# PWR_CORE.net
KiCad netlist of a schematic drawn in Altium Designer
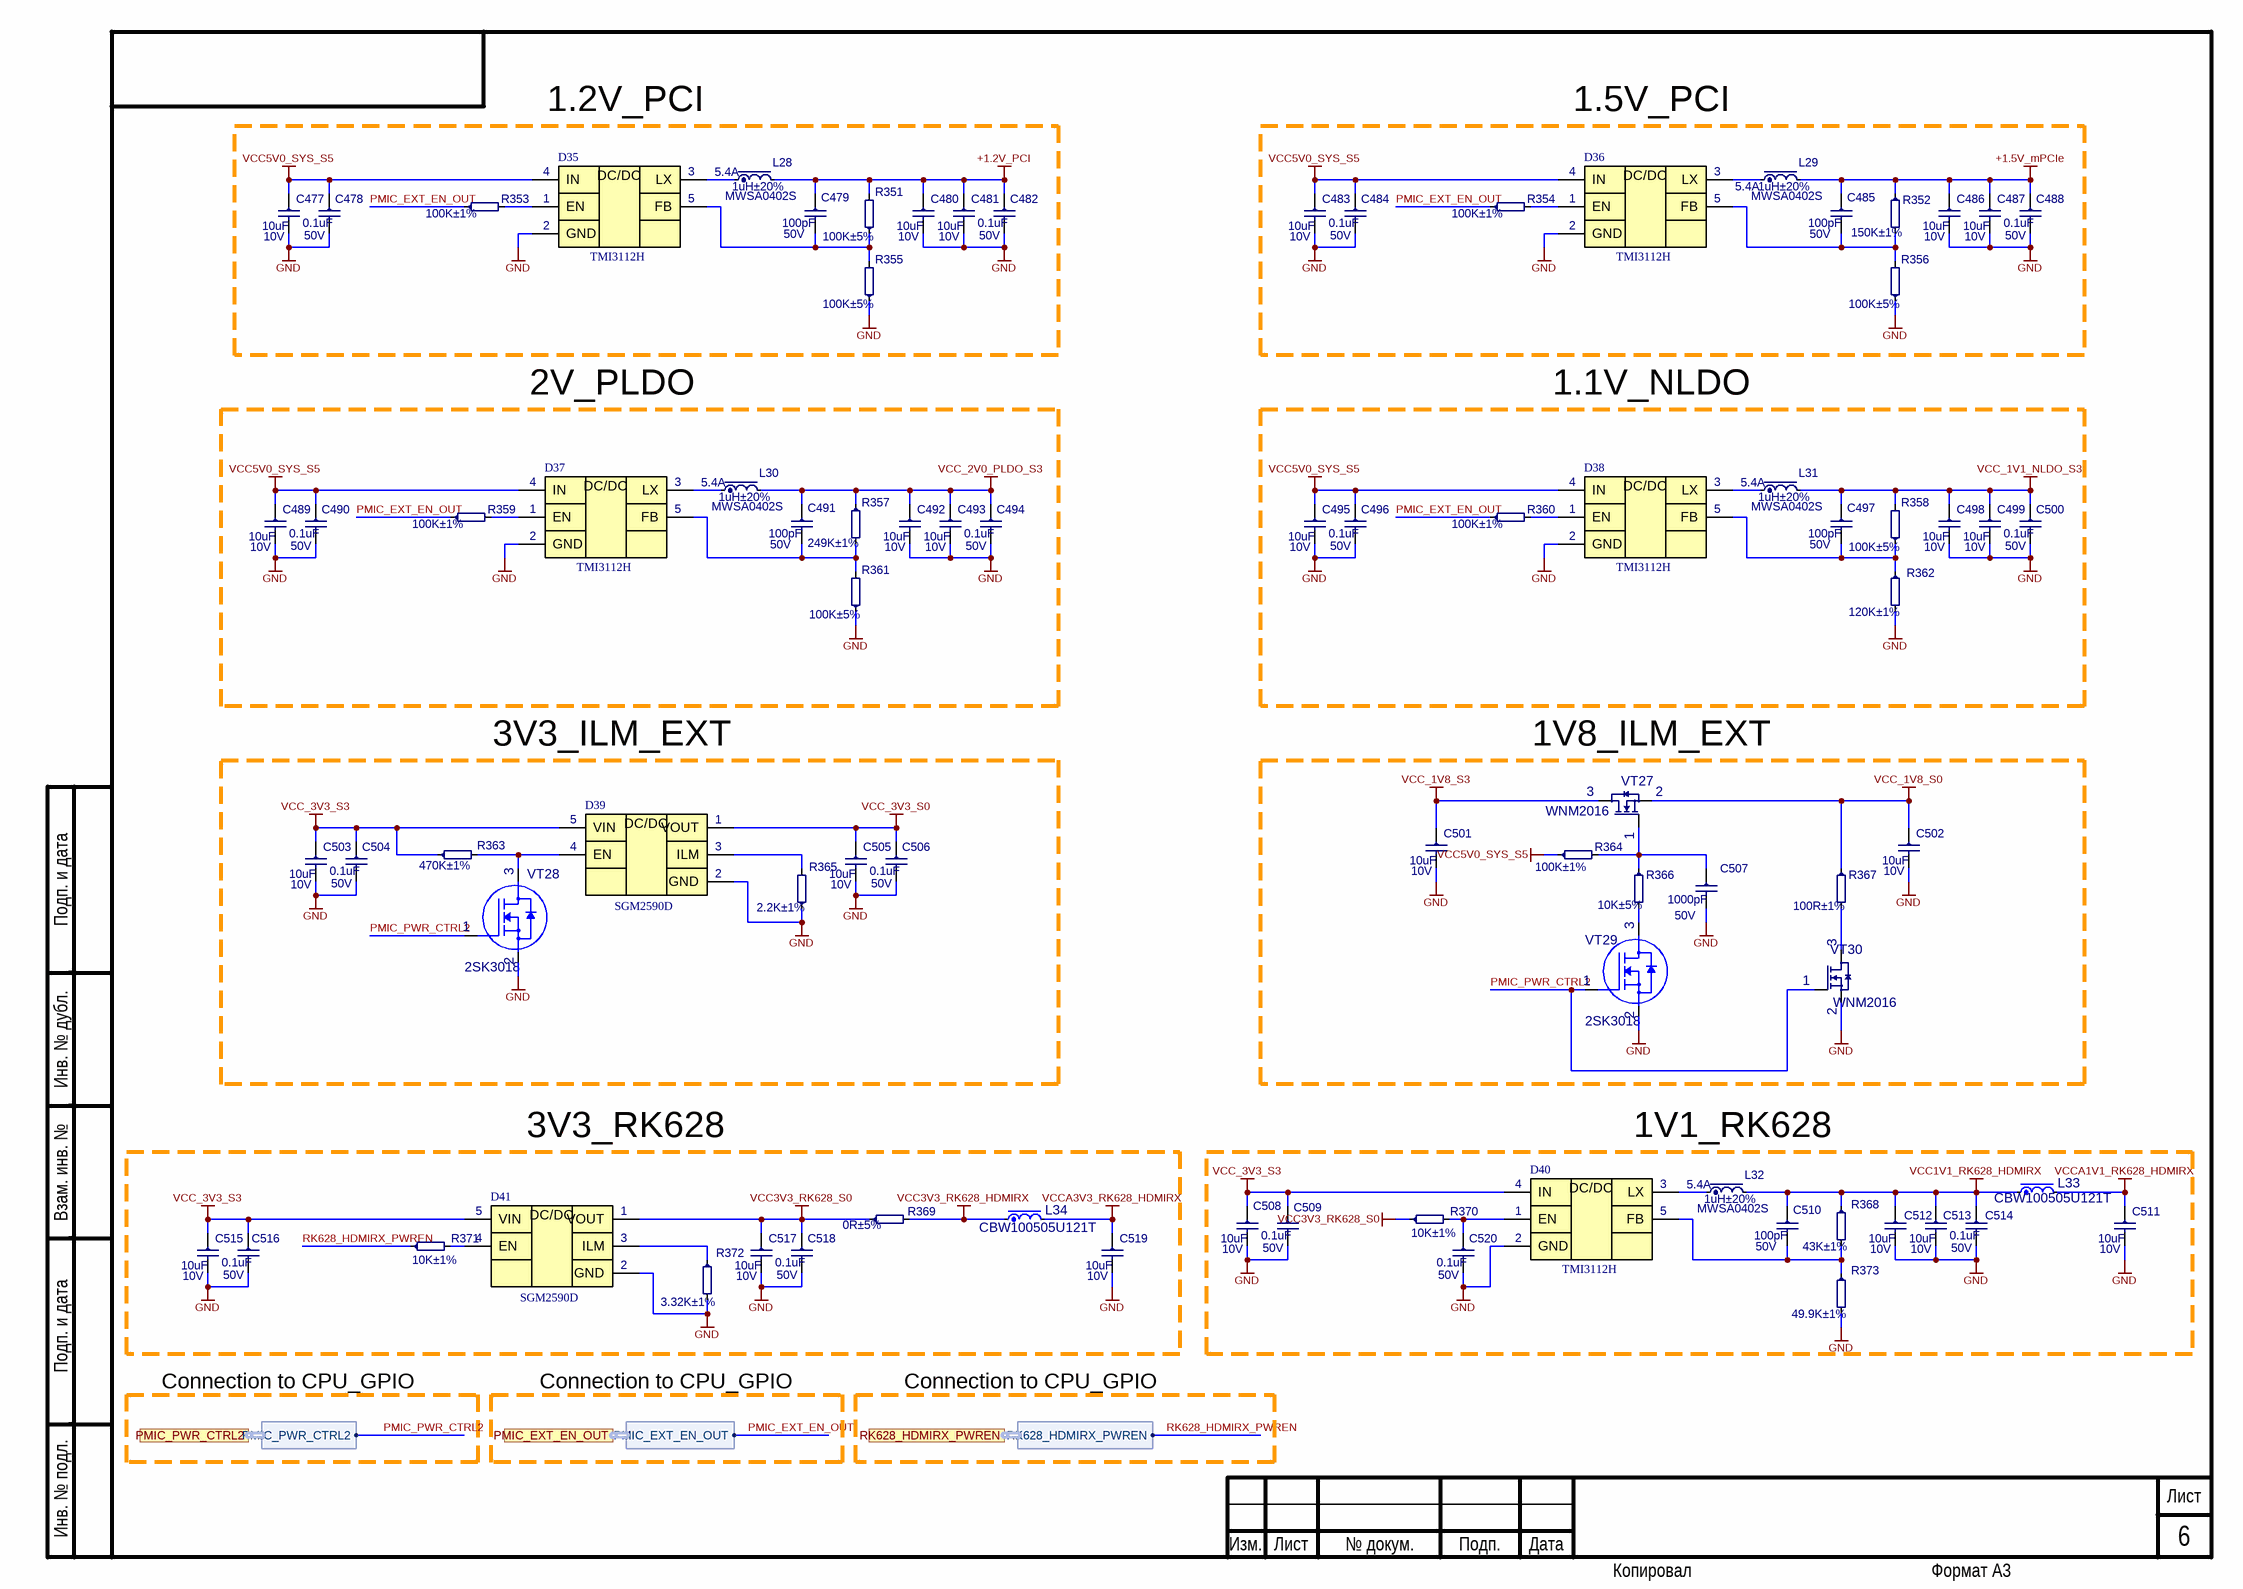
[diagram p0: PWR_CORE.SchDoc]

(export (version "E")
  (design (tool "Eeschema 10.0.6"))
  (components
    (comp (ref "C477")
      (value "10uF")
      (footprint "C0603")
      (fields
        (field (name "VOLTAGE") "10V")
        (field (name "PART NUMBER") "0603-X5R-10V-10uF±10%")
        (field (name "TOLERANCE") "10%")
        (field (name "MANUFACTURER") "Yageo")
      )
      (libsource (lib "ATB") (part "C"))
    )
    (comp (ref "C478")
      (value "0.1uF")
      (footprint "C0402")
      (fields
        (field (name "VOLTAGE") "50V")
        (field (name "PART NUMBER") "0402-X5R-50V-0.1uF±10%")
        (field (name "TOLERANCE") "10%")
        (field (name "MANUFACTURER") "Yageo")
      )
      (libsource (lib "ATB") (part "C"))
    )
    (comp (ref "C479")
      (value "100pF")
      (footprint "C0402")
      (fields
        (field (name "VOLTAGE") "50V")
        (field (name "PART NUMBER") "0402-NP0-50V-100pF±5%")
        (field (name "TOLERANCE") "5%")
        (field (name "MANUFACTURER") "Yageo")
      )
      (libsource (lib "ATB") (part "C"))
    )
    (comp (ref "C480")
      (value "10uF")
      (footprint "C0603")
      (fields
        (field (name "VOLTAGE") "10V")
        (field (name "PART NUMBER") "0603-X5R-10V-10uF±10%")
        (field (name "TOLERANCE") "10%")
        (field (name "MANUFACTURER") "Yageo")
      )
      (libsource (lib "ATB") (part "C"))
    )
    (comp (ref "C481")
      (value "10uF")
      (footprint "C0603")
      (fields
        (field (name "VOLTAGE") "10V")
        (field (name "PART NUMBER") "0603-X5R-10V-10uF±10%")
        (field (name "TOLERANCE") "10%")
        (field (name "MANUFACTURER") "Yageo")
      )
      (libsource (lib "ATB") (part "C"))
    )
    (comp (ref "C482")
      (value "0.1uF")
      (footprint "C0402")
      (fields
        (field (name "VOLTAGE") "50V")
        (field (name "PART NUMBER") "0402-X5R-50V-0.1uF±10%")
        (field (name "TOLERANCE") "10%")
        (field (name "MANUFACTURER") "Yageo")
      )
      (libsource (lib "ATB") (part "C"))
    )
    (comp (ref "C483")
      (value "10uF")
      (footprint "C0603")
      (fields
        (field (name "VOLTAGE") "10V")
        (field (name "PART NUMBER") "0603-X5R-10V-10uF±10%")
        (field (name "TOLERANCE") "10%")
        (field (name "MANUFACTURER") "Yageo")
      )
      (libsource (lib "ATB") (part "C"))
    )
    (comp (ref "C484")
      (value "0.1uF")
      (footprint "C0402")
      (fields
        (field (name "VOLTAGE") "50V")
        (field (name "PART NUMBER") "0402-X5R-50V-0.1uF±10%")
        (field (name "TOLERANCE") "10%")
        (field (name "MANUFACTURER") "Yageo")
      )
      (libsource (lib "ATB") (part "C"))
    )
    (comp (ref "C485")
      (value "100pF")
      (footprint "C0402")
      (fields
        (field (name "VOLTAGE") "50V")
        (field (name "PART NUMBER") "0402-NP0-50V-100pF±5%")
        (field (name "TOLERANCE") "5%")
        (field (name "MANUFACTURER") "Yageo")
      )
      (libsource (lib "ATB") (part "C"))
    )
    (comp (ref "C486")
      (value "10uF")
      (footprint "C0603")
      (fields
        (field (name "VOLTAGE") "10V")
        (field (name "PART NUMBER") "0603-X5R-10V-10uF±10%")
        (field (name "TOLERANCE") "10%")
        (field (name "MANUFACTURER") "Yageo")
      )
      (libsource (lib "ATB") (part "C"))
    )
    (comp (ref "C487")
      (value "10uF")
      (footprint "C0603")
      (fields
        (field (name "VOLTAGE") "10V")
        (field (name "PART NUMBER") "0603-X5R-10V-10uF±10%")
        (field (name "TOLERANCE") "10%")
        (field (name "MANUFACTURER") "Yageo")
      )
      (libsource (lib "ATB") (part "C"))
    )
    (comp (ref "C488")
      (value "0.1uF")
      (footprint "C0402")
      (fields
        (field (name "VOLTAGE") "50V")
        (field (name "PART NUMBER") "0402-X5R-50V-0.1uF±10%")
        (field (name "TOLERANCE") "10%")
        (field (name "MANUFACTURER") "Yageo")
      )
      (libsource (lib "ATB") (part "C"))
    )
    (comp (ref "C489")
      (value "10uF")
      (footprint "C0603")
      (fields
        (field (name "VOLTAGE") "10V")
        (field (name "PART NUMBER") "0603-X5R-10V-10uF±10%")
        (field (name "TOLERANCE") "10%")
        (field (name "MANUFACTURER") "Yageo")
      )
      (libsource (lib "ATB") (part "C"))
    )
    (comp (ref "C490")
      (value "0.1uF")
      (footprint "C0402")
      (fields
        (field (name "VOLTAGE") "50V")
        (field (name "PART NUMBER") "0402-X5R-50V-0.1uF±10%")
        (field (name "TOLERANCE") "10%")
        (field (name "MANUFACTURER") "Yageo")
      )
      (libsource (lib "ATB") (part "C"))
    )
    (comp (ref "C491")
      (value "100pF")
      (footprint "C0402")
      (fields
        (field (name "VOLTAGE") "50V")
        (field (name "PART NUMBER") "0402-NP0-50V-100pF±5%")
        (field (name "TOLERANCE") "5%")
        (field (name "MANUFACTURER") "Yageo")
      )
      (libsource (lib "ATB") (part "C"))
    )
    (comp (ref "C492")
      (value "10uF")
      (footprint "C0603")
      (fields
        (field (name "VOLTAGE") "10V")
        (field (name "PART NUMBER") "0603-X5R-10V-10uF±10%")
        (field (name "TOLERANCE") "10%")
        (field (name "MANUFACTURER") "Yageo")
      )
      (libsource (lib "ATB") (part "C"))
    )
    (comp (ref "C493")
      (value "10uF")
      (footprint "C0603")
      (fields
        (field (name "VOLTAGE") "10V")
        (field (name "PART NUMBER") "0603-X5R-10V-10uF±10%")
        (field (name "TOLERANCE") "10%")
        (field (name "MANUFACTURER") "Yageo")
      )
      (libsource (lib "ATB") (part "C"))
    )
    (comp (ref "C494")
      (value "0.1uF")
      (footprint "C0402")
      (fields
        (field (name "VOLTAGE") "50V")
        (field (name "PART NUMBER") "0402-X5R-50V-0.1uF±10%")
        (field (name "TOLERANCE") "10%")
        (field (name "MANUFACTURER") "Yageo")
      )
      (libsource (lib "ATB") (part "C"))
    )
    (comp (ref "C495")
      (value "10uF")
      (footprint "C0603")
      (fields
        (field (name "VOLTAGE") "10V")
        (field (name "PART NUMBER") "0603-X5R-10V-10uF±10%")
        (field (name "TOLERANCE") "10%")
        (field (name "MANUFACTURER") "Yageo")
      )
      (libsource (lib "ATB") (part "C"))
    )
    (comp (ref "C496")
      (value "0.1uF")
      (footprint "C0402")
      (fields
        (field (name "VOLTAGE") "50V")
        (field (name "PART NUMBER") "0402-X5R-50V-0.1uF±10%")
        (field (name "TOLERANCE") "10%")
        (field (name "MANUFACTURER") "Yageo")
      )
      (libsource (lib "ATB") (part "C"))
    )
    (comp (ref "C497")
      (value "100pF")
      (footprint "C0402")
      (fields
        (field (name "VOLTAGE") "50V")
        (field (name "PART NUMBER") "0402-NP0-50V-100pF±5%")
        (field (name "TOLERANCE") "5%")
        (field (name "MANUFACTURER") "Yageo")
      )
      (libsource (lib "ATB") (part "C"))
    )
    (comp (ref "C498")
      (value "10uF")
      (footprint "C0603")
      (fields
        (field (name "VOLTAGE") "10V")
        (field (name "PART NUMBER") "0603-X5R-10V-10uF±10%")
        (field (name "TOLERANCE") "10%")
        (field (name "MANUFACTURER") "Yageo")
      )
      (libsource (lib "ATB") (part "C"))
    )
    (comp (ref "C499")
      (value "10uF")
      (footprint "C0603")
      (fields
        (field (name "VOLTAGE") "10V")
        (field (name "PART NUMBER") "0603-X5R-10V-10uF±10%")
        (field (name "TOLERANCE") "10%")
        (field (name "MANUFACTURER") "Yageo")
      )
      (libsource (lib "ATB") (part "C"))
    )
    (comp (ref "C500")
      (value "0.1uF")
      (footprint "C0402")
      (fields
        (field (name "VOLTAGE") "50V")
        (field (name "PART NUMBER") "0402-X5R-50V-0.1uF±10%")
        (field (name "TOLERANCE") "10%")
        (field (name "MANUFACTURER") "Yageo")
      )
      (libsource (lib "ATB") (part "C"))
    )
    (comp (ref "C501")
      (value "10uF")
      (footprint "C0603")
      (fields
        (field (name "VOLTAGE") "10V")
        (field (name "PART NUMBER") "0603-X5R-10V-10uF±10%")
        (field (name "TOLERANCE") "10%")
        (field (name "MANUFACTURER") "Yageo")
      )
      (libsource (lib "ATB") (part "C"))
    )
    (comp (ref "C502")
      (value "10uF")
      (footprint "C0603")
      (fields
        (field (name "VOLTAGE") "10V")
        (field (name "PART NUMBER") "0603-X5R-10V-10uF±10%")
        (field (name "TOLERANCE") "10%")
        (field (name "MANUFACTURER") "Yageo")
      )
      (libsource (lib "ATB") (part "C"))
    )
    (comp (ref "C503")
      (value "10uF")
      (footprint "C0603")
      (fields
        (field (name "VOLTAGE") "10V")
        (field (name "PART NUMBER") "0603-X5R-10V-10uF±10%")
        (field (name "TOLERANCE") "10%")
        (field (name "MANUFACTURER") "Yageo")
      )
      (libsource (lib "ATB") (part "C"))
    )
    (comp (ref "C504")
      (value "0.1uF")
      (footprint "C0402")
      (fields
        (field (name "VOLTAGE") "50V")
        (field (name "PART NUMBER") "0402-X5R-50V-0.1uF±10%")
        (field (name "TOLERANCE") "10%")
        (field (name "MANUFACTURER") "Yageo")
      )
      (libsource (lib "ATB") (part "C"))
    )
    (comp (ref "C505")
      (value "10uF")
      (footprint "C0603")
      (fields
        (field (name "VOLTAGE") "10V")
        (field (name "PART NUMBER") "0603-X5R-10V-10uF±10%")
        (field (name "TOLERANCE") "10%")
        (field (name "MANUFACTURER") "Yageo")
      )
      (libsource (lib "ATB") (part "C"))
    )
    (comp (ref "C506")
      (value "0.1uF")
      (footprint "C0402")
      (fields
        (field (name "VOLTAGE") "50V")
        (field (name "PART NUMBER") "0402-X5R-50V-0.1uF±10%")
        (field (name "TOLERANCE") "10%")
        (field (name "MANUFACTURER") "Yageo")
      )
      (libsource (lib "ATB") (part "C"))
    )
    (comp (ref "C507")
      (value "1000pF")
      (footprint "C0402")
      (fields
        (field (name "VOLTAGE") "50V")
        (field (name "PART NUMBER") "0402-NP0-50V-1000pF±5%")
        (field (name "TOLERANCE") "5%")
        (field (name "MANUFACTURER") "Yageo")
      )
      (libsource (lib "ATB") (part "C"))
    )
    (comp (ref "C508")
      (value "10uF")
      (footprint "C0603")
      (fields
        (field (name "VOLTAGE") "10V")
        (field (name "PART NUMBER") "0603-X5R-10V-10uF±10%")
        (field (name "TOLERANCE") "10%")
        (field (name "MANUFACTURER") "Yageo")
      )
      (libsource (lib "ATB") (part "C"))
    )
    (comp (ref "C509")
      (value "0.1uF")
      (footprint "C0402")
      (fields
        (field (name "VOLTAGE") "50V")
        (field (name "PART NUMBER") "0402-X5R-50V-0.1uF±10%")
        (field (name "TOLERANCE") "10%")
        (field (name "MANUFACTURER") "Yageo")
      )
      (libsource (lib "ATB") (part "C"))
    )
    (comp (ref "C510")
      (value "100pF")
      (footprint "C0402")
      (fields
        (field (name "VOLTAGE") "50V")
        (field (name "PART NUMBER") "0402-NP0-50V-100pF±5%")
        (field (name "TOLERANCE") "5%")
        (field (name "MANUFACTURER") "Yageo")
      )
      (libsource (lib "ATB") (part "C"))
    )
    (comp (ref "C511")
      (value "10uF")
      (footprint "C0603")
      (fields
        (field (name "VOLTAGE") "10V")
        (field (name "PART NUMBER") "0603-X5R-10V-10uF±10%")
        (field (name "TOLERANCE") "10%")
        (field (name "MANUFACTURER") "Yageo")
      )
      (libsource (lib "ATB") (part "C"))
    )
    (comp (ref "C512")
      (value "10uF")
      (footprint "C0603")
      (fields
        (field (name "VOLTAGE") "10V")
        (field (name "PART NUMBER") "0603-X5R-10V-10uF±10%")
        (field (name "TOLERANCE") "10%")
        (field (name "MANUFACTURER") "Yageo")
      )
      (libsource (lib "ATB") (part "C"))
    )
    (comp (ref "C513")
      (value "10uF")
      (footprint "C0603")
      (fields
        (field (name "VOLTAGE") "10V")
        (field (name "PART NUMBER") "0603-X5R-10V-10uF±10%")
        (field (name "TOLERANCE") "10%")
        (field (name "MANUFACTURER") "Yageo")
      )
      (libsource (lib "ATB") (part "C"))
    )
    (comp (ref "C514")
      (value "0.1uF")
      (footprint "C0402")
      (fields
        (field (name "VOLTAGE") "50V")
        (field (name "PART NUMBER") "0402-X5R-50V-0.1uF±10%")
        (field (name "TOLERANCE") "10%")
        (field (name "MANUFACTURER") "Yageo")
      )
      (libsource (lib "ATB") (part "C"))
    )
    (comp (ref "C515")
      (value "10uF")
      (footprint "C0603")
      (fields
        (field (name "VOLTAGE") "10V")
        (field (name "PART NUMBER") "0603-X5R-10V-10uF±10%")
        (field (name "TOLERANCE") "10%")
        (field (name "MANUFACTURER") "Yageo")
      )
      (libsource (lib "ATB") (part "C"))
    )
    (comp (ref "C516")
      (value "0.1uF")
      (footprint "C0402")
      (fields
        (field (name "VOLTAGE") "50V")
        (field (name "PART NUMBER") "0402-X5R-50V-0.1uF±10%")
        (field (name "TOLERANCE") "10%")
        (field (name "MANUFACTURER") "Yageo")
      )
      (libsource (lib "ATB") (part "C"))
    )
    (comp (ref "C517")
      (value "10uF")
      (footprint "C0603")
      (fields
        (field (name "VOLTAGE") "10V")
        (field (name "PART NUMBER") "0603-X5R-10V-10uF±10%")
        (field (name "TOLERANCE") "10%")
        (field (name "MANUFACTURER") "Yageo")
      )
      (libsource (lib "ATB") (part "C"))
    )
    (comp (ref "C518")
      (value "0.1uF")
      (footprint "C0402")
      (fields
        (field (name "VOLTAGE") "50V")
        (field (name "PART NUMBER") "0402-X5R-50V-0.1uF±10%")
        (field (name "TOLERANCE") "10%")
        (field (name "MANUFACTURER") "Yageo")
      )
      (libsource (lib "ATB") (part "C"))
    )
    (comp (ref "C519")
      (value "10uF")
      (footprint "C0603")
      (fields
        (field (name "VOLTAGE") "10V")
        (field (name "PART NUMBER") "0603-X5R-10V-10uF±10%")
        (field (name "TOLERANCE") "10%")
        (field (name "MANUFACTURER") "Yageo")
      )
      (libsource (lib "ATB") (part "C"))
    )
    (comp (ref "C520")
      (value "0.1uF")
      (footprint "C0402")
      (fields
        (field (name "VOLTAGE") "50V")
        (field (name "PART NUMBER") "0402-X5R-50V-0.1uF±10%")
        (field (name "TOLERANCE") "10%")
        (field (name "MANUFACTURER") "Yageo")
      )
      (libsource (lib "ATB") (part "C"))
    )
    (comp (ref "D35")
      (value "TMI3112H")
      (footprint "TMI3112H")
      (description "Buck 2.3MHz Adjustable 2A 600mV~5.5V SOT-23-5 Voltage Regulators - DC DC Switching Regulators RoHS")
      (fields (field (name "MANUFACTURER") "TMI"))
      (libsource (lib "LIB_RK") (part "TMI3112H"))
    )
    (comp (ref "D36")
      (value "TMI3112H")
      (footprint "TMI3112H")
      (description "Buck 2.3MHz Adjustable 2A 600mV~5.5V SOT-23-5 Voltage Regulators - DC DC Switching Regulators RoHS")
      (fields (field (name "MANUFACTURER") "TMI"))
      (libsource (lib "LIB_RK") (part "TMI3112H"))
    )
    (comp (ref "D37")
      (value "TMI3112H")
      (footprint "TMI3112H")
      (description "Buck 2.3MHz Adjustable 2A 600mV~5.5V SOT-23-5 Voltage Regulators - DC DC Switching Regulators RoHS")
      (fields (field (name "MANUFACTURER") "TMI"))
      (libsource (lib "LIB_RK") (part "TMI3112H"))
    )
    (comp (ref "D38")
      (value "TMI3112H")
      (footprint "TMI3112H")
      (description "Buck 2.3MHz Adjustable 2A 600mV~5.5V SOT-23-5 Voltage Regulators - DC DC Switching Regulators RoHS")
      (fields (field (name "MANUFACTURER") "TMI"))
      (libsource (lib "LIB_RK") (part "TMI3112H"))
    )
    (comp (ref "D39")
      (value "SGM2590D")
      (footprint "SGM2590D")
      (fields (field (name "MANUFACTURER") "SGM"))
      (libsource (lib "LIB_RK") (part "SGM2590D"))
    )
    (comp (ref "D40")
      (value "TMI3112H")
      (footprint "TMI3112H")
      (description "Buck 2.3MHz Adjustable 2A 600mV~5.5V SOT-23-5 Voltage Regulators - DC DC Switching Regulators RoHS")
      (fields (field (name "MANUFACTURER") "TMI"))
      (libsource (lib "LIB_RK") (part "TMI3112H"))
    )
    (comp (ref "D41")
      (value "SGM2590D")
      (footprint "SGM2590D")
      (fields (field (name "MANUFACTURER") "SGM"))
      (libsource (lib "LIB_RK") (part "SGM2590D"))
    )
    (comp (ref "L28")
      (value "1uH±20%")
      (footprint "MWSA0402S")
      (description "5.4A 1uH ±20% 5.6A SMD 4.4x4.2mm Power Inductor")
      (fields
        (field (name "CURRENT") "5.4A")
        (field (name "CASE") "MWSA0402S")
        (field (name "PART NUMBER") "MWSA0402S-1R0MT")
        (field (name "TOLERANCE") "20%")
      )
      (libsource (lib "ATB") (part "L"))
    )
    (comp (ref "L29")
      (value "1uH±20%")
      (footprint "MWSA0402S")
      (description "5.4A 1uH ±20% 5.6A SMD 4.4x4.2mm Power Inductor")
      (fields
        (field (name "CURRENT") "5.4A")
        (field (name "CASE") "MWSA0402S")
        (field (name "PART NUMBER") "MWSA0402S-1R0MT")
        (field (name "TOLERANCE") "20%")
      )
      (libsource (lib "ATB") (part "L"))
    )
    (comp (ref "L30")
      (value "1uH±20%")
      (footprint "MWSA0402S")
      (description "5.4A 1uH ±20% 5.6A SMD 4.4x4.2mm Power Inductor")
      (fields
        (field (name "CURRENT") "5.4A")
        (field (name "CASE") "MWSA0402S")
        (field (name "PART NUMBER") "MWSA0402S-1R0MT")
        (field (name "TOLERANCE") "20%")
      )
      (libsource (lib "ATB") (part "L"))
    )
    (comp (ref "L31")
      (value "1uH±20%")
      (footprint "MWSA0402S")
      (description "5.4A 1uH ±20% 5.6A SMD 4.4x4.2mm Power Inductor")
      (fields
        (field (name "CURRENT") "5.4A")
        (field (name "CASE") "MWSA0402S")
        (field (name "PART NUMBER") "MWSA0402S-1R0MT")
        (field (name "TOLERANCE") "20%")
      )
      (libsource (lib "ATB") (part "L"))
    )
    (comp (ref "L32")
      (value "1uH±20%")
      (footprint "MWSA0402S")
      (description "5.4A 1uH ±20% 5.6A SMD 4.4x4.2mm Power Inductor")
      (fields
        (field (name "CURRENT") "5.4A")
        (field (name "CASE") "MWSA0402S")
        (field (name "PART NUMBER") "MWSA0402S-1R0MT")
        (field (name "TOLERANCE") "20%")
      )
      (libsource (lib "ATB") (part "L"))
    )
    (comp (ref "L33")
      (value "CBW100505U121T")
      (footprint "L0402")
      (description "120Ω@100MHz  Ferrite Beads")
      (fields (field (name "TOLERANCE") "25%") (field (name "MANUFACTURER") "Murata Electronics"))
      (libsource (lib "") (part "L_1"))
    )
    (comp (ref "L34")
      (value "CBW100505U121T")
      (footprint "L0402")
      (description "120Ω@100MHz  Ferrite Beads")
      (fields (field (name "TOLERANCE") "25%") (field (name "MANUFACTURER") "Murata Electronics"))
      (libsource (lib "") (part "L_1"))
    )
    (comp (ref "R351")
      (value "100K±5%")
      (footprint "R0402")
      (fields
        (field (name "PART NUMBER") "0402-0.0625W-100K-100ppm±5%")
        (field (name "TOLERANCE") "5%")
        (field (name "MANUFACTURER") "Yageo")
      )
      (libsource (lib "ATB") (part "R"))
    )
    (comp (ref "R352")
      (value "150K±1%")
      (footprint "R0402")
      (fields
        (field (name "PART NUMBER") "0402-0.0625W-150K-100ppm±1%")
        (field (name "TOLERANCE") "1%")
        (field (name "MANUFACTURER") "Yageo")
      )
      (libsource (lib "ATB") (part "R"))
    )
    (comp (ref "R353")
      (value "100K±1%")
      (footprint "R0402")
      (description "Chip Resistor 0402 100kΩ ±1% 50V ±100ppm/℃ Thick Film")
      (fields (field (name "PART NUMBER") "0402-0.0625W-100K-100ppm±1%") (field (name "TOLERANCE") "1%"))
      (libsource (lib "ATB") (part "R"))
    )
    (comp (ref "R354")
      (value "100K±1%")
      (footprint "R0402")
      (description "Chip Resistor 0402 100kΩ ±1% 50V ±100ppm/℃ Thick Film")
      (fields (field (name "PART NUMBER") "0402-0.0625W-100K-100ppm±1%") (field (name "TOLERANCE") "1%"))
      (libsource (lib "ATB") (part "R"))
    )
    (comp (ref "R355")
      (value "100K±5%")
      (footprint "R0402")
      (fields
        (field (name "PART NUMBER") "0402-0.0625W-100K-100ppm±5%")
        (field (name "TOLERANCE") "5%")
        (field (name "MANUFACTURER") "Yageo")
      )
      (libsource (lib "ATB") (part "R"))
    )
    (comp (ref "R356")
      (value "100K±5%")
      (footprint "R0402")
      (fields
        (field (name "PART NUMBER") "0402-0.0625W-100K-100ppm±5%")
        (field (name "TOLERANCE") "5%")
        (field (name "MANUFACTURER") "Yageo")
      )
      (libsource (lib "ATB") (part "R"))
    )
    (comp (ref "R357")
      (value "249K±1%")
      (footprint "R0402")
      (fields
        (field (name "PART NUMBER") "0402-0.0625W-249K-100ppm±1%")
        (field (name "TOLERANCE") "1%")
        (field (name "MANUFACTURER") "Yageo")
      )
      (libsource (lib "ATB") (part "R"))
    )
    (comp (ref "R358")
      (value "100K±5%")
      (footprint "R0402")
      (fields
        (field (name "PART NUMBER") "0402-0.0625W-100K-100ppm±5%")
        (field (name "TOLERANCE") "5%")
        (field (name "MANUFACTURER") "Yageo")
      )
      (libsource (lib "ATB") (part "R"))
    )
    (comp (ref "R359")
      (value "100K±1%")
      (footprint "R0402")
      (description "Chip Resistor 0402 100kΩ ±1% 50V ±100ppm/℃ Thick Film")
      (fields (field (name "PART NUMBER") "0402-0.0625W-100K-100ppm±1%") (field (name "TOLERANCE") "1%"))
      (libsource (lib "ATB") (part "R"))
    )
    (comp (ref "R360")
      (value "100K±1%")
      (footprint "R0402")
      (description "Chip Resistor 0402 100kΩ ±1% 50V ±100ppm/℃ Thick Film")
      (fields (field (name "PART NUMBER") "0402-0.0625W-100K-100ppm±1%") (field (name "TOLERANCE") "1%"))
      (libsource (lib "ATB") (part "R"))
    )
    (comp (ref "R361")
      (value "100K±5%")
      (footprint "R0402")
      (fields
        (field (name "PART NUMBER") "0402-0.0625W-100K-100ppm±5%")
        (field (name "TOLERANCE") "5%")
        (field (name "MANUFACTURER") "Yageo")
      )
      (libsource (lib "ATB") (part "R"))
    )
    (comp (ref "R362")
      (value "120K±1%")
      (footprint "R0402")
      (fields
        (field (name "PART NUMBER") "0402-0.0625W-120K-100ppm±1%")
        (field (name "TOLERANCE") "1%")
        (field (name "MANUFACTURER") "Yageo")
      )
      (libsource (lib "ATB") (part "R"))
    )
    (comp (ref "R363")
      (value "470K±1%")
      (footprint "R0402")
      (fields
        (field (name "PART NUMBER") "0402-0.0625W-470K-100ppm±1%")
        (field (name "TOLERANCE") "1%")
        (field (name "MANUFACTURER") "Yageo")
      )
      (libsource (lib "ATB") (part "R"))
    )
    (comp (ref "R364")
      (value "100K±1%")
      (footprint "R0402")
      (description "Chip Resistor 0402 100kΩ ±1% 50V ±100ppm/℃ Thick Film")
      (fields (field (name "PART NUMBER") "0402-0.0625W-100K-100ppm±1%") (field (name "TOLERANCE") "1%"))
      (libsource (lib "ATB") (part "R"))
    )
    (comp (ref "R365")
      (value "2.2K±1%")
      (footprint "R0402")
      (fields
        (field (name "PART NUMBER") "0402-0.0625W-2.2K-100ppm±1%")
        (field (name "TOLERANCE") "1%")
        (field (name "MANUFACTURER") "Yageo")
      )
      (libsource (lib "ATB") (part "R"))
    )
    (comp (ref "R366")
      (value "10K±5%")
      (footprint "R0402")
      (fields
        (field (name "PART NUMBER") "0402-0.0625W-10K-100ppm±5%")
        (field (name "TOLERANCE") "5%")
        (field (name "MANUFACTURER") "Yageo")
      )
      (libsource (lib "ATB") (part "R"))
    )
    (comp (ref "R367")
      (value "100R±1%")
      (footprint "R0402")
      (description "Chip Resistor 0402 100Ω ±1% 50V ±100ppm/℃ Thick Film")
      (fields (field (name "PART NUMBER") "0402-0.0625W-100R-100ppm±1%") (field (name "TOLERANCE") "1%"))
      (libsource (lib "ATB") (part "R"))
    )
    (comp (ref "R368")
      (value "43K±1%")
      (footprint "R0402")
      (fields
        (field (name "PART NUMBER") "0402-0.0625W-43K-100ppm±1%")
        (field (name "TOLERANCE") "1%")
        (field (name "MANUFACTURER") "Yageo")
      )
      (libsource (lib "ATB") (part "R"))
    )
    (comp (ref "R369")
      (value "0R±5%")
      (footprint "R0603")
      (description "Chip Resistor 0603 0Ω ±5% 50V ±100ppm/℃ Thick Film")
      (fields (field (name "PART NUMBER") "0603-0.1W-0R-100ppm±5%") (field (name "TOLERANCE") "5%"))
      (libsource (lib "ATB") (part "R"))
    )
    (comp (ref "R370")
      (value "10K±1%")
      (footprint "R0402")
      (description "Chip Resistor 0402 10kΩ ±1% 50V ±100ppm/℃ Thick Film")
      (fields (field (name "PART NUMBER") "0402-0.0625W-10K-100ppm±1%") (field (name "TOLERANCE") "1%"))
      (libsource (lib "ATB") (part "R"))
    )
    (comp (ref "R371")
      (value "10K±1%")
      (footprint "R0402")
      (description "Chip Resistor 0402 10kΩ ±1% 50V ±100ppm/℃ Thick Film")
      (fields (field (name "PART NUMBER") "0402-0.0625W-10K-100ppm±1%") (field (name "TOLERANCE") "1%"))
      (libsource (lib "ATB") (part "R"))
    )
    (comp (ref "R372")
      (value "3.32K±1%")
      (footprint "R0603")
      (fields
        (field (name "PART NUMBER") "0603-0.1W-3.32K-100ppm±1%")
        (field (name "TOLERANCE") "1%")
        (field (name "MANUFACTURER") "Viking Tech Corp.(VIKING)")
      )
      (libsource (lib "ATB") (part "R"))
    )
    (comp (ref "R373")
      (value "49.9K±1%")
      (footprint "R0402")
      (description "Chip Resistor 0402 49.9kΩ ±1% 50V ±100ppm/℃ Thick Film")
      (fields (field (name "PART NUMBER") "0402-0.0625W-49.9K-100ppm±1%") (field (name "TOLERANCE") "1%"))
      (libsource (lib "ATB") (part "R"))
    )
    (comp (ref "VT27")
      (value "WNM2016")
      (footprint "SOT23")
      (description "60V 3A 0.35W Surface Mount SOT-23")
      (fields (field (name "VOLTAGE") "60V") (field (name "MANUFACTURER") "KUU Semiconductor"))
      (libsource (lib "ATB") (part "BSS138"))
    )
    (comp (ref "VT28")
      (value "2SK3018")
      (footprint "2SK3018")
      (description "N-Channel")
      (libsource (lib "LIB_RK") (part "2SK3018"))
    )
    (comp (ref "VT29")
      (value "2SK3018")
      (footprint "2SK3018")
      (description "N-Channel")
      (libsource (lib "LIB_RK") (part "2SK3018"))
    )
    (comp (ref "VT30")
      (value "WNM2016")
      (footprint "SOT23")
      (description "60V 3A 0.35W Surface Mount SOT-23")
      (fields (field (name "VOLTAGE") "60V") (field (name "MANUFACTURER") "KUU Semiconductor"))
      (libsource (lib "ATB") (part "BSS138"))
    )
  )
  (nets
    (net (code "1") (name "+1.2V_PCI") (class "Default")
      (node (ref "C479") (pin "1") (pinfunction "1_1") (pintype "passive"))
      (node (ref "C480") (pin "1") (pinfunction "1_1") (pintype "passive"))
      (node (ref "C481") (pin "1") (pinfunction "1_1") (pintype "passive"))
      (node (ref "C482") (pin "1") (pinfunction "1_1") (pintype "passive"))
      (node (ref "L28") (pin "2") (pinfunction "2_2") (pintype "passive"))
      (node (ref "R351") (pin "2") (pinfunction "2_2") (pintype "passive"))
    )
    (net (code "2") (name "+1.5V_mPCIe") (class "Default")
      (node (ref "C485") (pin "1") (pinfunction "1_1") (pintype "passive"))
      (node (ref "C486") (pin "1") (pinfunction "1_1") (pintype "passive"))
      (node (ref "C487") (pin "1") (pinfunction "1_1") (pintype "passive"))
      (node (ref "C488") (pin "1") (pinfunction "1_1") (pintype "passive"))
      (node (ref "L29") (pin "2") (pinfunction "2_2") (pintype "passive"))
      (node (ref "R352") (pin "1") (pinfunction "1_1") (pintype "passive"))
    )
    (net (code "3") (name "/PMIC_EXT_EN_OUT") (class "Default")
      (node (ref "R353") (pin "1") (pinfunction "1_1") (pintype "passive"))
      (node (ref "R354") (pin "1") (pinfunction "1_1") (pintype "passive"))
      (node (ref "R359") (pin "1") (pinfunction "1_1") (pintype "passive"))
      (node (ref "R360") (pin "1") (pinfunction "1_1") (pintype "passive"))
    )
    (net (code "4") (name "/PMIC_PWR_CTRL2") (class "Default")
      (node (ref "VT28") (pin "1") (pinfunction "G_1") (pintype "passive"))
      (node (ref "VT29") (pin "1") (pinfunction "G_1") (pintype "passive"))
      (node (ref "VT30") (pin "1") (pinfunction "G_1") (pintype "passive"))
    )
    (net (code "5") (name "/RK628_HDMIRX_PWREN") (class "Default")
      (node (ref "R371") (pin "1") (pinfunction "1_1") (pintype "passive"))
    )
    (net (code "9") (name "GND") (class "Default")
      (node (ref "C477") (pin "2") (pinfunction "2_2") (pintype "passive"))
      (node (ref "C478") (pin "2") (pinfunction "2_2") (pintype "passive"))
      (node (ref "C480") (pin "2") (pinfunction "2_2") (pintype "passive"))
      (node (ref "C481") (pin "2") (pinfunction "2_2") (pintype "passive"))
      (node (ref "C482") (pin "2") (pinfunction "2_2") (pintype "passive"))
      (node (ref "C483") (pin "2") (pinfunction "2_2") (pintype "passive"))
      (node (ref "C484") (pin "2") (pinfunction "2_2") (pintype "passive"))
      (node (ref "C486") (pin "2") (pinfunction "2_2") (pintype "passive"))
      (node (ref "C487") (pin "2") (pinfunction "2_2") (pintype "passive"))
      (node (ref "C488") (pin "2") (pinfunction "2_2") (pintype "passive"))
      (node (ref "C489") (pin "2") (pinfunction "2_2") (pintype "passive"))
      (node (ref "C490") (pin "2") (pinfunction "2_2") (pintype "passive"))
      (node (ref "C492") (pin "2") (pinfunction "2_2") (pintype "passive"))
      (node (ref "C493") (pin "2") (pinfunction "2_2") (pintype "passive"))
      (node (ref "C494") (pin "2") (pinfunction "2_2") (pintype "passive"))
      (node (ref "C495") (pin "2") (pinfunction "2_2") (pintype "passive"))
      (node (ref "C496") (pin "2") (pinfunction "2_2") (pintype "passive"))
      (node (ref "C498") (pin "2") (pinfunction "2_2") (pintype "passive"))
      (node (ref "C499") (pin "2") (pinfunction "2_2") (pintype "passive"))
      (node (ref "C500") (pin "2") (pinfunction "2_2") (pintype "passive"))
      (node (ref "C501") (pin "2") (pinfunction "2_2") (pintype "passive"))
      (node (ref "C502") (pin "2") (pinfunction "2_2") (pintype "passive"))
      (node (ref "C503") (pin "2") (pinfunction "2_2") (pintype "passive"))
      (node (ref "C504") (pin "2") (pinfunction "2_2") (pintype "passive"))
      (node (ref "C505") (pin "2") (pinfunction "2_2") (pintype "passive"))
      (node (ref "C506") (pin "2") (pinfunction "2_2") (pintype "passive"))
      (node (ref "C507") (pin "2") (pinfunction "2_2") (pintype "passive"))
      (node (ref "C508") (pin "2") (pinfunction "2_2") (pintype "passive"))
      (node (ref "C509") (pin "2") (pinfunction "2_2") (pintype "passive"))
      (node (ref "C511") (pin "2") (pinfunction "2_2") (pintype "passive"))
      (node (ref "C512") (pin "2") (pinfunction "2_2") (pintype "passive"))
      (node (ref "C513") (pin "2") (pinfunction "2_2") (pintype "passive"))
      (node (ref "C514") (pin "2") (pinfunction "2_2") (pintype "passive"))
      (node (ref "C515") (pin "2") (pinfunction "2_2") (pintype "passive"))
      (node (ref "C516") (pin "2") (pinfunction "2_2") (pintype "passive"))
      (node (ref "C517") (pin "2") (pinfunction "2_2") (pintype "passive"))
      (node (ref "C518") (pin "2") (pinfunction "2_2") (pintype "passive"))
      (node (ref "C519") (pin "2") (pinfunction "2_2") (pintype "passive"))
      (node (ref "C520") (pin "2") (pinfunction "2_2") (pintype "passive"))
      (node (ref "D35") (pin "2") (pinfunction "GND_2") (pintype "passive"))
      (node (ref "D36") (pin "2") (pinfunction "GND_2") (pintype "passive"))
      (node (ref "D37") (pin "2") (pinfunction "GND_2") (pintype "passive"))
      (node (ref "D38") (pin "2") (pinfunction "GND_2") (pintype "passive"))
      (node (ref "D39") (pin "2") (pinfunction "GND_2") (pintype "passive"))
      (node (ref "D40") (pin "2") (pinfunction "GND_2") (pintype "passive"))
      (node (ref "D41") (pin "2") (pinfunction "GND_2") (pintype "passive"))
      (node (ref "R355") (pin "1") (pinfunction "1_1") (pintype "passive"))
      (node (ref "R356") (pin "1") (pinfunction "1_1") (pintype "passive"))
      (node (ref "R361") (pin "1") (pinfunction "1_1") (pintype "passive"))
      (node (ref "R362") (pin "2") (pinfunction "2_2") (pintype "passive"))
      (node (ref "R365") (pin "1") (pinfunction "1_1") (pintype "passive"))
      (node (ref "R372") (pin "2") (pinfunction "2_2") (pintype "passive"))
      (node (ref "R373") (pin "2") (pinfunction "2_2") (pintype "passive"))
      (node (ref "VT28") (pin "2") (pinfunction "S_2") (pintype "passive"))
      (node (ref "VT29") (pin "2") (pinfunction "S_2") (pintype "passive"))
      (node (ref "VT30") (pin "2") (pinfunction "S_2") (pintype "passive"))
    )
    (net (code "10") (name "Net-(D35-EN)") (class "Default")
      (node (ref "D35") (pin "1") (pinfunction "EN_1") (pintype "passive"))
      (node (ref "R353") (pin "2") (pinfunction "2_2") (pintype "passive"))
    )
    (net (code "11") (name "Net-(D35-FB)") (class "Default")
      (node (ref "C479") (pin "2") (pinfunction "2_2") (pintype "passive"))
      (node (ref "D35") (pin "5") (pinfunction "FB_5") (pintype "passive"))
      (node (ref "R351") (pin "1") (pinfunction "1_1") (pintype "passive"))
      (node (ref "R355") (pin "2") (pinfunction "2_2") (pintype "passive"))
    )
    (net (code "12") (name "Net-(D35-LX)") (class "Default")
      (node (ref "D35") (pin "3") (pinfunction "LX_3") (pintype "passive"))
      (node (ref "L28") (pin "1") (pinfunction "1_1") (pintype "passive"))
    )
    (net (code "13") (name "Net-(D36-EN)") (class "Default")
      (node (ref "D36") (pin "1") (pinfunction "EN_1") (pintype "passive"))
      (node (ref "R354") (pin "2") (pinfunction "2_2") (pintype "passive"))
    )
    (net (code "14") (name "Net-(D36-FB)") (class "Default")
      (node (ref "C485") (pin "2") (pinfunction "2_2") (pintype "passive"))
      (node (ref "D36") (pin "5") (pinfunction "FB_5") (pintype "passive"))
      (node (ref "R352") (pin "2") (pinfunction "2_2") (pintype "passive"))
      (node (ref "R356") (pin "2") (pinfunction "2_2") (pintype "passive"))
    )
    (net (code "15") (name "Net-(D36-LX)") (class "Default")
      (node (ref "D36") (pin "3") (pinfunction "LX_3") (pintype "passive"))
      (node (ref "L29") (pin "1") (pinfunction "1_1") (pintype "passive"))
    )
    (net (code "16") (name "Net-(D37-EN)") (class "Default")
      (node (ref "D37") (pin "1") (pinfunction "EN_1") (pintype "passive"))
      (node (ref "R359") (pin "2") (pinfunction "2_2") (pintype "passive"))
    )
    (net (code "17") (name "Net-(D37-FB)") (class "Default")
      (node (ref "C491") (pin "2") (pinfunction "2_2") (pintype "passive"))
      (node (ref "D37") (pin "5") (pinfunction "FB_5") (pintype "passive"))
      (node (ref "R357") (pin "2") (pinfunction "2_2") (pintype "passive"))
      (node (ref "R361") (pin "2") (pinfunction "2_2") (pintype "passive"))
    )
    (net (code "18") (name "Net-(D37-LX)") (class "Default")
      (node (ref "D37") (pin "3") (pinfunction "LX_3") (pintype "passive"))
      (node (ref "L30") (pin "1") (pinfunction "1_1") (pintype "passive"))
    )
    (net (code "19") (name "Net-(D38-EN)") (class "Default")
      (node (ref "D38") (pin "1") (pinfunction "EN_1") (pintype "passive"))
      (node (ref "R360") (pin "2") (pinfunction "2_2") (pintype "passive"))
    )
    (net (code "20") (name "Net-(D38-FB)") (class "Default")
      (node (ref "C497") (pin "2") (pinfunction "2_2") (pintype "passive"))
      (node (ref "D38") (pin "5") (pinfunction "FB_5") (pintype "passive"))
      (node (ref "R358") (pin "1") (pinfunction "1_1") (pintype "passive"))
      (node (ref "R362") (pin "1") (pinfunction "1_1") (pintype "passive"))
    )
    (net (code "21") (name "Net-(D38-LX)") (class "Default")
      (node (ref "D38") (pin "3") (pinfunction "LX_3") (pintype "passive"))
      (node (ref "L31") (pin "1") (pinfunction "1_1") (pintype "passive"))
    )
    (net (code "22") (name "Net-(D39-EN)") (class "Default")
      (node (ref "D39") (pin "4") (pinfunction "EN_4") (pintype "passive"))
      (node (ref "R363") (pin "2") (pinfunction "2_2") (pintype "passive"))
      (node (ref "VT28") (pin "3") (pinfunction "D_3") (pintype "passive"))
    )
    (net (code "23") (name "Net-(D39-ILM)") (class "Default")
      (node (ref "D39") (pin "3") (pinfunction "ILM_3") (pintype "passive"))
      (node (ref "R365") (pin "2") (pinfunction "2_2") (pintype "passive"))
    )
    (net (code "24") (name "Net-(D40-EN)") (class "Default")
      (node (ref "C520") (pin "1") (pinfunction "1_1") (pintype "passive"))
      (node (ref "D40") (pin "1") (pinfunction "EN_1") (pintype "passive"))
      (node (ref "R370") (pin "2") (pinfunction "2_2") (pintype "passive"))
    )
    (net (code "25") (name "Net-(D40-FB)") (class "Default")
      (node (ref "C510") (pin "2") (pinfunction "2_2") (pintype "passive"))
      (node (ref "D40") (pin "5") (pinfunction "FB_5") (pintype "passive"))
      (node (ref "R368") (pin "2") (pinfunction "2_2") (pintype "passive"))
      (node (ref "R373") (pin "1") (pinfunction "1_1") (pintype "passive"))
    )
    (net (code "26") (name "Net-(D40-LX)") (class "Default")
      (node (ref "D40") (pin "3") (pinfunction "LX_3") (pintype "passive"))
      (node (ref "L32") (pin "1") (pinfunction "1_1") (pintype "passive"))
    )
    (net (code "27") (name "Net-(D41-EN)") (class "Default")
      (node (ref "D41") (pin "4") (pinfunction "EN_4") (pintype "passive"))
      (node (ref "R371") (pin "2") (pinfunction "2_2") (pintype "passive"))
    )
    (net (code "28") (name "Net-(D41-ILM)") (class "Default")
      (node (ref "D41") (pin "3") (pinfunction "ILM_3") (pintype "passive"))
      (node (ref "R372") (pin "1") (pinfunction "1_1") (pintype "passive"))
    )
    (net (code "29") (name "Net-(VT27-G)") (class "Default")
      (node (ref "C507") (pin "1") (pinfunction "1_1") (pintype "passive"))
      (node (ref "R364") (pin "2") (pinfunction "2_2") (pintype "passive"))
      (node (ref "R366") (pin "1") (pinfunction "1_1") (pintype "passive"))
      (node (ref "VT27") (pin "1") (pinfunction "G_1") (pintype "passive"))
    )
    (net (code "30") (name "Net-(VT29-D)") (class "Default")
      (node (ref "R366") (pin "2") (pinfunction "2_2") (pintype "passive"))
      (node (ref "VT29") (pin "3") (pinfunction "D_3") (pintype "passive"))
    )
    (net (code "31") (name "Net-(VT30-D)") (class "Default")
      (node (ref "R367") (pin "2") (pinfunction "2_2") (pintype "passive"))
      (node (ref "VT30") (pin "3") (pinfunction "D_3") (pintype "passive"))
    )
    (net (code "32") (name "VCC1V1_RK628_HDMIRX") (class "Default")
      (node (ref "C510") (pin "1") (pinfunction "1_1") (pintype "passive"))
      (node (ref "C512") (pin "1") (pinfunction "1_1") (pintype "passive"))
      (node (ref "C513") (pin "1") (pinfunction "1_1") (pintype "passive"))
      (node (ref "C514") (pin "1") (pinfunction "1_1") (pintype "passive"))
      (node (ref "L32") (pin "2") (pinfunction "2_2") (pintype "passive"))
      (node (ref "L33") (pin "1") (pinfunction "1_1") (pintype "passive"))
      (node (ref "R368") (pin "1") (pinfunction "1_1") (pintype "passive"))
    )
    (net (code "33") (name "VCC3V3_RK628_HDMIRX") (class "Default")
      (node (ref "L34") (pin "1") (pinfunction "1_1") (pintype "passive"))
      (node (ref "R369") (pin "2") (pinfunction "2_2") (pintype "passive"))
    )
    (net (code "34") (name "VCC3V3_RK628_S0") (class "Default")
      (node (ref "C517") (pin "1") (pinfunction "1_1") (pintype "passive"))
      (node (ref "C518") (pin "1") (pinfunction "1_1") (pintype "passive"))
      (node (ref "D41") (pin "1") (pinfunction "VOUT_1") (pintype "passive"))
      (node (ref "R369") (pin "1") (pinfunction "1_1") (pintype "passive"))
      (node (ref "R370") (pin "1") (pinfunction "1_1") (pintype "passive"))
    )
    (net (code "35") (name "VCC5V0_SYS_S5") (class "Default")
      (node (ref "C477") (pin "1") (pinfunction "1_1") (pintype "passive"))
      (node (ref "C478") (pin "1") (pinfunction "1_1") (pintype "passive"))
      (node (ref "C483") (pin "1") (pinfunction "1_1") (pintype "passive"))
      (node (ref "C484") (pin "1") (pinfunction "1_1") (pintype "passive"))
      (node (ref "C489") (pin "1") (pinfunction "1_1") (pintype "passive"))
      (node (ref "C490") (pin "1") (pinfunction "1_1") (pintype "passive"))
      (node (ref "C495") (pin "1") (pinfunction "1_1") (pintype "passive"))
      (node (ref "C496") (pin "1") (pinfunction "1_1") (pintype "passive"))
      (node (ref "D35") (pin "4") (pinfunction "IN_4") (pintype "passive"))
      (node (ref "D36") (pin "4") (pinfunction "IN_4") (pintype "passive"))
      (node (ref "D37") (pin "4") (pinfunction "IN_4") (pintype "passive"))
      (node (ref "D38") (pin "4") (pinfunction "IN_4") (pintype "passive"))
      (node (ref "R364") (pin "1") (pinfunction "1_1") (pintype "passive"))
    )
    (net (code "36") (name "VCCA1V1_RK628_HDMIRX") (class "Default")
      (node (ref "C511") (pin "1") (pinfunction "1_1") (pintype "passive"))
      (node (ref "L33") (pin "2") (pinfunction "2_2") (pintype "passive"))
    )
    (net (code "37") (name "VCCA3V3_RK628_HDMIRX") (class "Default")
      (node (ref "C519") (pin "1") (pinfunction "1_1") (pintype "passive"))
      (node (ref "L34") (pin "2") (pinfunction "2_2") (pintype "passive"))
    )
    (net (code "38") (name "VCC_1V1_NLDO_S3") (class "Default")
      (node (ref "C497") (pin "1") (pinfunction "1_1") (pintype "passive"))
      (node (ref "C498") (pin "1") (pinfunction "1_1") (pintype "passive"))
      (node (ref "C499") (pin "1") (pinfunction "1_1") (pintype "passive"))
      (node (ref "C500") (pin "1") (pinfunction "1_1") (pintype "passive"))
      (node (ref "L31") (pin "2") (pinfunction "2_2") (pintype "passive"))
      (node (ref "R358") (pin "2") (pinfunction "2_2") (pintype "passive"))
    )
    (net (code "39") (name "VCC_1V8_S0") (class "Default")
      (node (ref "C502") (pin "1") (pinfunction "1_1") (pintype "passive"))
      (node (ref "R367") (pin "1") (pinfunction "1_1") (pintype "passive"))
      (node (ref "VT27") (pin "2") (pinfunction "S_2") (pintype "passive"))
    )
    (net (code "40") (name "VCC_1V8_S3") (class "Default")
      (node (ref "C501") (pin "1") (pinfunction "1_1") (pintype "passive"))
      (node (ref "VT27") (pin "3") (pinfunction "D_3") (pintype "passive"))
    )
    (net (code "41") (name "VCC_2V0_PLDO_S3") (class "Default")
      (node (ref "C491") (pin "1") (pinfunction "1_1") (pintype "passive"))
      (node (ref "C492") (pin "1") (pinfunction "1_1") (pintype "passive"))
      (node (ref "C493") (pin "1") (pinfunction "1_1") (pintype "passive"))
      (node (ref "C494") (pin "1") (pinfunction "1_1") (pintype "passive"))
      (node (ref "L30") (pin "2") (pinfunction "2_2") (pintype "passive"))
      (node (ref "R357") (pin "1") (pinfunction "1_1") (pintype "passive"))
    )
    (net (code "42") (name "VCC_3V3_S0") (class "Default")
      (node (ref "C505") (pin "1") (pinfunction "1_1") (pintype "passive"))
      (node (ref "C506") (pin "1") (pinfunction "1_1") (pintype "passive"))
      (node (ref "D39") (pin "1") (pinfunction "VOUT_1") (pintype "passive"))
    )
    (net (code "43") (name "VCC_3V3_S3") (class "Default")
      (node (ref "C503") (pin "1") (pinfunction "1_1") (pintype "passive"))
      (node (ref "C504") (pin "1") (pinfunction "1_1") (pintype "passive"))
      (node (ref "C508") (pin "1") (pinfunction "1_1") (pintype "passive"))
      (node (ref "C509") (pin "1") (pinfunction "1_1") (pintype "passive"))
      (node (ref "C515") (pin "1") (pinfunction "1_1") (pintype "passive"))
      (node (ref "C516") (pin "1") (pinfunction "1_1") (pintype "passive"))
      (node (ref "D39") (pin "5") (pinfunction "VIN_5") (pintype "passive"))
      (node (ref "D40") (pin "4") (pinfunction "IN_4") (pintype "passive"))
      (node (ref "D41") (pin "5") (pinfunction "VIN_5") (pintype "passive"))
      (node (ref "R363") (pin "1") (pinfunction "1_1") (pintype "passive"))
    )
  )
)
